# ProProject_si5351-clock_2024-06-27.net
KiCad netlist of a schematic drawn in EasyEDA Pro
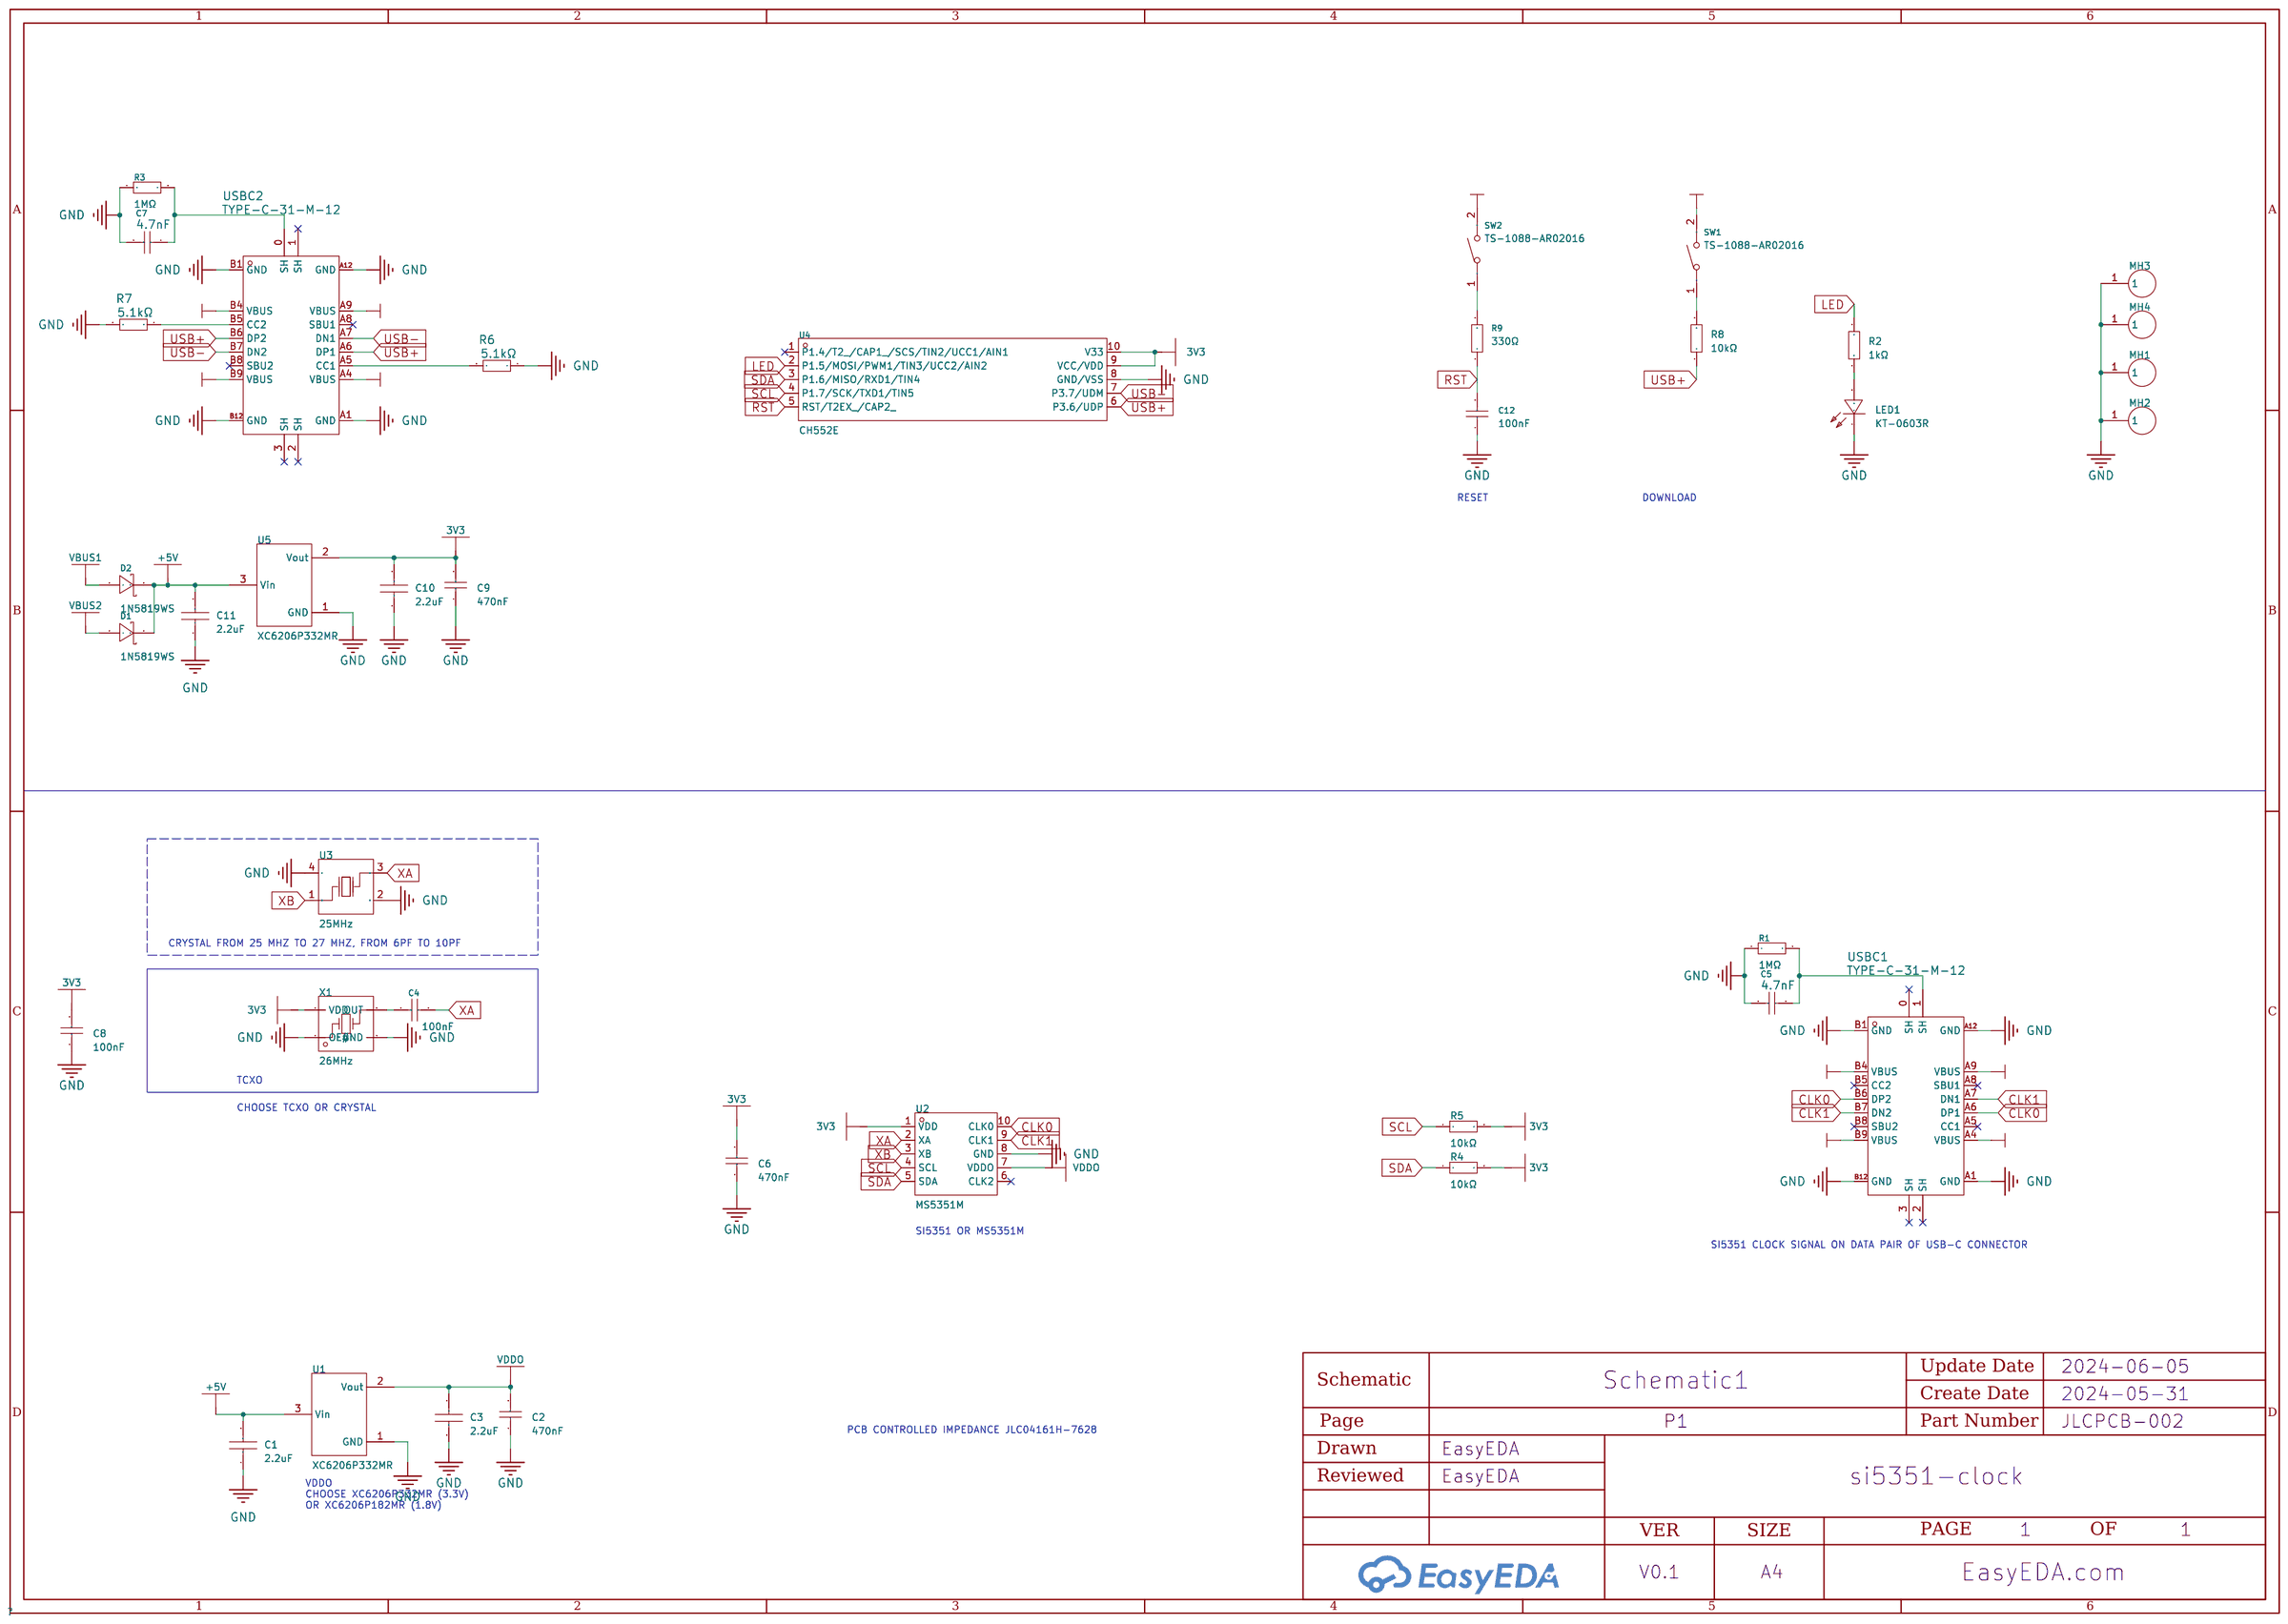
[diagram p0: schematic sheet]

(export (version "E")
  (design (tool "Eeschema 10.0.6"))
  (components
    (comp (ref "C1")
      (value "2.2uF")
      (footprint "easyedapro:C0402")
      (fields
        (field (name "Manufacturer Part") "CL05A225MQ5NSNC")
        (field (name "Manufacturer") "SAMSUNG(三星)")
      )
      (libsource (lib "easyedapro") (part "CL05A225MQ5NSNC"))
    )
    (comp (ref "C2")
      (value "470nF")
      (footprint "easyedapro:C0402")
      (fields
        (field (name "Manufacturer Part") "CL05A474KP5NNNC")
        (field (name "Manufacturer") "SAMSUNG(三星)")
      )
      (libsource (lib "easyedapro") (part "CL05A474KP5NNNC"))
    )
    (comp (ref "C3")
      (value "2.2uF")
      (footprint "easyedapro:C0402")
      (fields
        (field (name "Manufacturer Part") "CL05A225MQ5NSNC")
        (field (name "Manufacturer") "SAMSUNG(三星)")
      )
      (libsource (lib "easyedapro") (part "CL05A225MQ5NSNC"))
    )
    (comp (ref "C4")
      (value "100nF")
      (footprint "easyedapro:C0402")
      (fields
        (field (name "Manufacturer Part") "CL05B104KO5NNNC")
        (field (name "Manufacturer") "SAMSUNG(三星)")
      )
      (libsource (lib "easyedapro") (part "CL05B104KO5NNNC"))
    )
    (comp (ref "C5")
      (value "4.7nF")
      (footprint "easyedapro:C0402")
      (fields (field (name "Manufacturer Part") "0402B472K500NT") (field (name "Manufacturer") "FH(风华)"))
      (libsource (lib "easyedapro") (part "4.7nF"))
    )
    (comp (ref "C6")
      (value "470nF")
      (footprint "easyedapro:C0402")
      (fields
        (field (name "Manufacturer Part") "CL05A474KP5NNNC")
        (field (name "Manufacturer") "SAMSUNG(三星)")
      )
      (libsource (lib "easyedapro") (part "CL05A474KP5NNNC"))
    )
    (comp (ref "C7")
      (value "4.7nF")
      (footprint "easyedapro:C0402")
      (fields (field (name "Manufacturer Part") "0402B472K500NT") (field (name "Manufacturer") "FH(风华)"))
      (libsource (lib "easyedapro") (part "4.7nF"))
    )
    (comp (ref "C8")
      (value "100nF")
      (footprint "easyedapro:C0402")
      (fields
        (field (name "Manufacturer Part") "CL05B104KO5NNNC")
        (field (name "Manufacturer") "SAMSUNG(三星)")
      )
      (libsource (lib "easyedapro") (part "CL05B104KO5NNNC"))
    )
    (comp (ref "C9")
      (value "470nF")
      (footprint "easyedapro:C0402")
      (fields
        (field (name "Manufacturer Part") "CL05A474KP5NNNC")
        (field (name "Manufacturer") "SAMSUNG(三星)")
      )
      (libsource (lib "easyedapro") (part "CL05A474KP5NNNC"))
    )
    (comp (ref "C10")
      (value "2.2uF")
      (footprint "easyedapro:C0402")
      (fields
        (field (name "Manufacturer Part") "CL05A225MQ5NSNC")
        (field (name "Manufacturer") "SAMSUNG(三星)")
      )
      (libsource (lib "easyedapro") (part "CL05A225MQ5NSNC"))
    )
    (comp (ref "C11")
      (value "2.2uF")
      (footprint "easyedapro:C0402")
      (fields
        (field (name "Manufacturer Part") "CL05A225MQ5NSNC")
        (field (name "Manufacturer") "SAMSUNG(三星)")
      )
      (libsource (lib "easyedapro") (part "CL05A225MQ5NSNC"))
    )
    (comp (ref "C12")
      (value "100nF")
      (footprint "easyedapro:C0402")
      (fields
        (field (name "Manufacturer Part") "CL05B104KO5NNNC")
        (field (name "Manufacturer") "SAMSUNG(三星)")
      )
      (libsource (lib "easyedapro") (part "CL05B104KO5NNNC"))
    )
    (comp (ref "D1")
      (value "1N5819WS")
      (footprint "easyedapro:SOD-323_L1.8-W1.3-LS2.5-RD")
      (description "Forward Voltage (Vf@If):600mV@1A Reverse Voltage (Vr):40V Average Rectified Current (Io):1A")
      (fields (field (name "Manufacturer") "Hottech(合科泰)"))
      (libsource (lib "easyedapro") (part "1N5819WS"))
    )
    (comp (ref "D2")
      (value "1N5819WS")
      (footprint "easyedapro:SOD-323_L1.8-W1.3-LS2.5-RD")
      (description "Forward Voltage (Vf@If):600mV@1A Reverse Voltage (Vr):40V Average Rectified Current (Io):1A")
      (fields (field (name "Manufacturer") "Hottech(合科泰)"))
      (libsource (lib "easyedapro") (part "1N5819WS"))
    )
    (comp (ref "LED1")
      (value "KT-0603R")
      (footprint "easyedapro:LED0603-RD")
      (fields (field (name "Manufacturer") "KENTO"))
      (libsource (lib "easyedapro") (part "KT-0603R"))
    )
    (comp (ref "MH1")
      (value "~")
      (footprint "easyedapro:3.2mm MountingHole")
      (description "M3")
      (libsource (lib "easyedapro") (part "3.2mm Mounting Hole"))
    )
    (comp (ref "MH2")
      (value "~")
      (footprint "easyedapro:3.2mm MountingHole")
      (description "M3")
      (libsource (lib "easyedapro") (part "3.2mm Mounting Hole"))
    )
    (comp (ref "MH3")
      (value "~")
      (footprint "easyedapro:3.2mm MountingHole")
      (description "M3")
      (libsource (lib "easyedapro") (part "3.2mm Mounting Hole"))
    )
    (comp (ref "MH4")
      (value "~")
      (footprint "easyedapro:3.2mm MountingHole")
      (description "M3")
      (libsource (lib "easyedapro") (part "3.2mm Mounting Hole"))
    )
    (comp (ref "R1")
      (value "1MΩ")
      (footprint "easyedapro:R0402")
      (fields
        (field (name "Manufacturer Part") "0402WGF1004TCE")
        (field (name "Manufacturer") "UNI-ROYAL(厚声)")
      )
      (libsource (lib "easyedapro") (part "0402WGF1004TCE"))
    )
    (comp (ref "R2")
      (value "1kΩ")
      (footprint "easyedapro:R0402")
      (fields
        (field (name "Manufacturer Part") "0402WGF1001TCE")
        (field (name "Manufacturer") "UNI-ROYAL(厚声)")
      )
      (libsource (lib "easyedapro") (part "0402WGF1001TCE"))
    )
    (comp (ref "R3")
      (value "1MΩ")
      (footprint "easyedapro:R0402")
      (fields
        (field (name "Manufacturer Part") "0402WGF1004TCE")
        (field (name "Manufacturer") "UNI-ROYAL(厚声)")
      )
      (libsource (lib "easyedapro") (part "0402WGF1004TCE"))
    )
    (comp (ref "R4")
      (value "10kΩ")
      (footprint "easyedapro:R0402")
      (fields
        (field (name "Manufacturer Part") "0402WGF1002TCE")
        (field (name "Manufacturer") "UNI-ROYAL(厚声)")
      )
      (libsource (lib "easyedapro") (part "0402WGF1002TCE"))
    )
    (comp (ref "R5")
      (value "10kΩ")
      (footprint "easyedapro:R0402")
      (fields
        (field (name "Manufacturer Part") "0402WGF1002TCE")
        (field (name "Manufacturer") "UNI-ROYAL(厚声)")
      )
      (libsource (lib "easyedapro") (part "0402WGF1002TCE"))
    )
    (comp (ref "R6")
      (value "5.1kΩ")
      (footprint "easyedapro:R0402")
      (fields
        (field (name "Manufacturer Part") "0402WGF5101TCE")
        (field (name "Manufacturer") "UNI-ROYAL(厚声)")
      )
      (libsource (lib "easyedapro") (part "5.1kΩ"))
    )
    (comp (ref "R7")
      (value "5.1kΩ")
      (footprint "easyedapro:R0402")
      (fields
        (field (name "Manufacturer Part") "0402WGF5101TCE")
        (field (name "Manufacturer") "UNI-ROYAL(厚声)")
      )
      (libsource (lib "easyedapro") (part "5.1kΩ"))
    )
    (comp (ref "R8")
      (value "10kΩ")
      (footprint "easyedapro:R0402")
      (fields
        (field (name "Manufacturer Part") "0402WGF1002TCE")
        (field (name "Manufacturer") "UNI-ROYAL(厚声)")
      )
      (libsource (lib "easyedapro") (part "0402WGF1002TCE"))
    )
    (comp (ref "R9")
      (value "330Ω")
      (footprint "easyedapro:R0402")
      (fields
        (field (name "Manufacturer Part") "0402WGF3300TCE")
        (field (name "Manufacturer") "UNI-ROYAL(厚声)")
      )
      (libsource (lib "easyedapro") (part "0402WGF3300TCE"))
    )
    (comp (ref "SW1")
      (value "TS-1088-AR02016")
      (footprint "easyedapro:SW-SMD_L3.9-W3.0-P4.45")
      (fields (field (name "Manufacturer") "XUNPU(讯普)"))
      (libsource (lib "easyedapro") (part "TS-1088-AR02016"))
    )
    (comp (ref "SW2")
      (value "TS-1088-AR02016")
      (footprint "easyedapro:SW-SMD_L3.9-W3.0-P4.45")
      (fields (field (name "Manufacturer") "XUNPU(讯普)"))
      (libsource (lib "easyedapro") (part "TS-1088-AR02016"))
    )
    (comp (ref "U1")
      (value "XC6206P332MR")
      (footprint "easyedapro:SOT-23-3_L2.9-W1.6-P1.90-LS2.8-BR")
      (fields (field (name "Manufacturer") "TOREX(特瑞仕)"))
      (libsource (lib "easyedapro") (part "XC6206P332MR"))
    )
    (comp (ref "U2")
      (value "MS5351M")
      (footprint "easyedapro:MSOP-10_L3.0-W3.0-P0.50-LS5.0-BL")
      (fields (field (name "Manufacturer") "杭州瑞盟"))
      (libsource (lib "easyedapro") (part "MS5351M"))
    )
    (comp (ref "U3")
      (value "25MHz")
      (footprint "easyedapro:CRYSTAL-SMD_4P-L3.2-W2.5-BL-1")
      (fields
        (field (name "Manufacturer Part") "3225-25-10-10-10/A")
        (field (name "Manufacturer") "LIMING(利明)")
      )
      (libsource (lib "easyedapro") (part "3225-25-10-10-10/A"))
    )
    (comp (ref "U4")
      (value "CH552E")
      (footprint "easyedapro:MSOP-10_L3.0-W3.0-P0.50-LS5.0-BL")
      (fields (field (name "Manufacturer") "WCH(南京沁恒)"))
      (libsource (lib "easyedapro") (part "CH552E"))
    )
    (comp (ref "U5")
      (value "XC6206P332MR")
      (footprint "easyedapro:SOT-23-3_L2.9-W1.6-P1.90-LS2.8-BR")
      (fields (field (name "Manufacturer") "TOREX(特瑞仕)"))
      (libsource (lib "easyedapro") (part "XC6206P332MR"))
    )
    (comp (ref "USBC1")
      (value "TYPE-C-31-M-12")
      (footprint "easyedapro:USB-C_SMD-TYPE-C-31-M-12")
      (fields (field (name "Manufacturer") "韩国韩荣"))
      (libsource (lib "easyedapro") (part "TYPE-C-31-M-12"))
    )
    (comp (ref "USBC2")
      (value "TYPE-C-31-M-12")
      (footprint "easyedapro:USB-C_SMD-TYPE-C-31-M-12")
      (fields (field (name "Manufacturer") "韩国韩荣"))
      (libsource (lib "easyedapro") (part "TYPE-C-31-M-12"))
    )
    (comp (ref "X1")
      (value "26MHz")
      (footprint "easyedapro:OSC-SMD_4P-L3.2-W2.5-BL_1XTV")
      (fields (field (name "Manufacturer Part") "1XTW26000MAA") (field (name "Manufacturer") "KDS(大真空)"))
      (libsource (lib "easyedapro") (part "1XTW26000MAA"))
    )
  )
  (nets
    (net (code "1") (name "+5V") (class "Default")
      (node (ref "C1") (pin "2") (pinfunction "2_2") (pintype "unspecified"))
      (node (ref "C11") (pin "2") (pinfunction "2_2") (pintype "unspecified"))
      (node (ref "D1") (pin "1") (pinfunction "K_1") (pintype "input"))
      (node (ref "D2") (pin "1") (pinfunction "K_1") (pintype "input"))
      (node (ref "U1") (pin "3") (pinfunction "Vin_3") (pintype "input"))
      (node (ref "U5") (pin "3") (pinfunction "Vin_3") (pintype "input"))
    )
    (net (code "2") (name "3V3") (class "Default")
      (node (ref "C10") (pin "2") (pinfunction "2_2") (pintype "unspecified"))
      (node (ref "C6") (pin "2") (pinfunction "2_2") (pintype "input"))
      (node (ref "C8") (pin "2") (pinfunction "2_2") (pintype "input"))
      (node (ref "C9") (pin "2") (pinfunction "2_2") (pintype "input"))
      (node (ref "R4") (pin "2") (pinfunction "2_2") (pintype "input"))
      (node (ref "R5") (pin "2") (pinfunction "2_2") (pintype "input"))
      (node (ref "SW1") (pin "2") (pinfunction "2_2") (pintype "input"))
      (node (ref "SW2") (pin "2") (pinfunction "2_2") (pintype "input"))
      (node (ref "U2") (pin "1") (pinfunction "VDD_1") (pintype "input"))
      (node (ref "U4") (pin "10") (pinfunction "V33_10") (pintype "input"))
      (node (ref "U4") (pin "9") (pinfunction "VCC/VDD_9") (pintype "input"))
      (node (ref "U5") (pin "2") (pinfunction "Vout_2") (pintype "input"))
      (node (ref "X1") (pin "4") (pinfunction "VDD_4") (pintype "input"))
    )
    (net (code "3") (name "CLK0") (class "Default")
      (node (ref "U2") (pin "10") (pinfunction "CLK0_10") (pintype "input"))
      (node (ref "USBC1") (pin "A6") (pinfunction "DP1_A6") (pintype "input"))
      (node (ref "USBC1") (pin "B6") (pinfunction "DP2_B6") (pintype "input"))
    )
    (net (code "4") (name "CLK1") (class "Default")
      (node (ref "U2") (pin "9") (pinfunction "CLK1_9") (pintype "input"))
      (node (ref "USBC1") (pin "A7") (pinfunction "DN1_A7") (pintype "input"))
      (node (ref "USBC1") (pin "B7") (pinfunction "DN2_B7") (pintype "input"))
    )
    (net (code "5") (name "GND") (class "Default")
      (node (ref "C1") (pin "1") (pinfunction "1_1") (pintype "unspecified"))
      (node (ref "C10") (pin "1") (pinfunction "1_1") (pintype "unspecified"))
      (node (ref "C11") (pin "1") (pinfunction "1_1") (pintype "unspecified"))
      (node (ref "C12") (pin "1") (pinfunction "1_1") (pintype "input"))
      (node (ref "C2") (pin "1") (pinfunction "1_1") (pintype "input"))
      (node (ref "C3") (pin "1") (pinfunction "1_1") (pintype "unspecified"))
      (node (ref "C5") (pin "1") (pinfunction "1_1") (pintype "input"))
      (node (ref "C6") (pin "1") (pinfunction "1_1") (pintype "input"))
      (node (ref "C7") (pin "1") (pinfunction "1_1") (pintype "input"))
      (node (ref "C8") (pin "1") (pinfunction "1_1") (pintype "input"))
      (node (ref "C9") (pin "1") (pinfunction "1_1") (pintype "input"))
      (node (ref "LED1") (pin "1") (pinfunction "K_1") (pintype "input"))
      (node (ref "MH1") (pin "1") (pinfunction "1_1") (pintype "input"))
      (node (ref "MH2") (pin "1") (pinfunction "1_1") (pintype "input"))
      (node (ref "MH3") (pin "1") (pinfunction "1_1") (pintype "input"))
      (node (ref "MH4") (pin "1") (pinfunction "1_1") (pintype "input"))
      (node (ref "R1") (pin "1") (pinfunction "1_1") (pintype "input"))
      (node (ref "R3") (pin "1") (pinfunction "1_1") (pintype "input"))
      (node (ref "R6") (pin "1") (pinfunction "1_1") (pintype "input"))
      (node (ref "R7") (pin "2") (pinfunction "2_2") (pintype "input"))
      (node (ref "U1") (pin "1") (pinfunction "GND_1") (pintype "input"))
      (node (ref "U2") (pin "8") (pinfunction "GND_8") (pintype "input"))
      (node (ref "U3") (pin "2") (pinfunction "GND_2") (pintype "unspecified"))
      (node (ref "U3") (pin "4") (pinfunction "GND_4") (pintype "unspecified"))
      (node (ref "U4") (pin "8") (pinfunction "GND/VSS_8") (pintype "input"))
      (node (ref "U5") (pin "1") (pinfunction "GND_1") (pintype "input"))
      (node (ref "USBC1") (pin "A1") (pinfunction "GND_A1") (pintype "input"))
      (node (ref "USBC1") (pin "A12") (pinfunction "GND_A12") (pintype "input"))
      (node (ref "USBC1") (pin "B1") (pinfunction "GND_B1") (pintype "input"))
      (node (ref "USBC1") (pin "B12") (pinfunction "GND_B12") (pintype "input"))
      (node (ref "USBC2") (pin "A1") (pinfunction "GND_A1") (pintype "input"))
      (node (ref "USBC2") (pin "A12") (pinfunction "GND_A12") (pintype "input"))
      (node (ref "USBC2") (pin "B1") (pinfunction "GND_B1") (pintype "input"))
      (node (ref "USBC2") (pin "B12") (pinfunction "GND_B12") (pintype "input"))
      (node (ref "X1") (pin "1") (pinfunction "OE#_1") (pintype "input"))
      (node (ref "X1") (pin "2") (pinfunction "GND_2") (pintype "input"))
    )
    (net (code "6") (name "LED") (class "Default")
      (node (ref "R2") (pin "2") (pinfunction "2_2") (pintype "input"))
      (node (ref "U4") (pin "2") (pinfunction "P1.5/MOSI/PWM1/TIN3/UCC2/AIN2_2") (pintype "input"))
    )
    (net (code "7") (name "Net-(C5-Pad2)") (class "Default")
      (node (ref "C5") (pin "2") (pinfunction "2_2") (pintype "input"))
      (node (ref "R1") (pin "2") (pinfunction "2_2") (pintype "input"))
      (node (ref "USBC1") (pin "1") (pinfunction "SH_1") (pintype "input"))
    )
    (net (code "8") (name "Net-(C7-Pad2)") (class "Default")
      (node (ref "C7") (pin "2") (pinfunction "2_2") (pintype "input"))
      (node (ref "R3") (pin "2") (pinfunction "2_2") (pintype "input"))
      (node (ref "USBC2") (pin "0") (pinfunction "SH_0") (pintype "input"))
    )
    (net (code "9") (name "Net-(LED1-A)") (class "Default")
      (node (ref "LED1") (pin "2") (pinfunction "A_2") (pintype "input"))
      (node (ref "R2") (pin "1") (pinfunction "1_1") (pintype "input"))
    )
    (net (code "10") (name "Net-(R8-Pad2)") (class "Default")
      (node (ref "R8") (pin "2") (pinfunction "2_2") (pintype "input"))
      (node (ref "SW1") (pin "1") (pinfunction "1_1") (pintype "input"))
    )
    (net (code "11") (name "Net-(R9-Pad2)") (class "Default")
      (node (ref "R9") (pin "2") (pinfunction "2_2") (pintype "input"))
      (node (ref "SW2") (pin "1") (pinfunction "1_1") (pintype "input"))
    )
    (net (code "12") (name "Net-(USBC2-CC1)") (class "Default")
      (node (ref "R6") (pin "2") (pinfunction "2_2") (pintype "input"))
      (node (ref "USBC2") (pin "A5") (pinfunction "CC1_A5") (pintype "input"))
    )
    (net (code "13") (name "Net-(USBC2-CC2)") (class "Default")
      (node (ref "R7") (pin "1") (pinfunction "1_1") (pintype "input"))
      (node (ref "USBC2") (pin "B5") (pinfunction "CC2_B5") (pintype "input"))
    )
    (net (code "14") (name "Net-(X1-OUT)") (class "Default")
      (node (ref "C4") (pin "1") (pinfunction "1_1") (pintype "input"))
      (node (ref "X1") (pin "3") (pinfunction "OUT_3") (pintype "input"))
    )
    (net (code "15") (name "RST") (class "Default")
      (node (ref "C12") (pin "2") (pinfunction "2_2") (pintype "input"))
      (node (ref "R9") (pin "1") (pinfunction "1_1") (pintype "input"))
      (node (ref "U4") (pin "5") (pinfunction "RST/T2EX_/CAP2__5") (pintype "input"))
    )
    (net (code "16") (name "SCL") (class "Default")
      (node (ref "R5") (pin "1") (pinfunction "1_1") (pintype "input"))
      (node (ref "U2") (pin "4") (pinfunction "SCL_4") (pintype "input"))
      (node (ref "U4") (pin "4") (pinfunction "P1.7/SCK/TXD1/TIN5_4") (pintype "input"))
    )
    (net (code "17") (name "SDA") (class "Default")
      (node (ref "R4") (pin "1") (pinfunction "1_1") (pintype "input"))
      (node (ref "U2") (pin "5") (pinfunction "SDA_5") (pintype "input"))
      (node (ref "U4") (pin "3") (pinfunction "P1.6/MISO/RXD1/TIN4_3") (pintype "input"))
    )
    (net (code "18") (name "USB+") (class "Default")
      (node (ref "R8") (pin "1") (pinfunction "1_1") (pintype "input"))
      (node (ref "U4") (pin "6") (pinfunction "P3.6/UDP_6") (pintype "input"))
      (node (ref "USBC2") (pin "A6") (pinfunction "DP1_A6") (pintype "input"))
      (node (ref "USBC2") (pin "B6") (pinfunction "DP2_B6") (pintype "input"))
    )
    (net (code "19") (name "USB-") (class "Default")
      (node (ref "U4") (pin "7") (pinfunction "P3.7/UDM_7") (pintype "input"))
      (node (ref "USBC2") (pin "A7") (pinfunction "DN1_A7") (pintype "input"))
      (node (ref "USBC2") (pin "B7") (pinfunction "DN2_B7") (pintype "input"))
    )
    (net (code "20") (name "VBUS1") (class "Default")
      (node (ref "D2") (pin "2") (pinfunction "A_2") (pintype "input"))
      (node (ref "USBC2") (pin "A4") (pinfunction "VBUS_A4") (pintype "input"))
      (node (ref "USBC2") (pin "A9") (pinfunction "VBUS_A9") (pintype "input"))
      (node (ref "USBC2") (pin "B4") (pinfunction "VBUS_B4") (pintype "input"))
      (node (ref "USBC2") (pin "B9") (pinfunction "VBUS_B9") (pintype "input"))
    )
    (net (code "21") (name "VBUS2") (class "Default")
      (node (ref "D1") (pin "2") (pinfunction "A_2") (pintype "input"))
      (node (ref "USBC1") (pin "A4") (pinfunction "VBUS_A4") (pintype "input"))
      (node (ref "USBC1") (pin "A9") (pinfunction "VBUS_A9") (pintype "input"))
      (node (ref "USBC1") (pin "B4") (pinfunction "VBUS_B4") (pintype "input"))
      (node (ref "USBC1") (pin "B9") (pinfunction "VBUS_B9") (pintype "input"))
    )
    (net (code "22") (name "VDDO") (class "Default")
      (node (ref "C2") (pin "2") (pinfunction "2_2") (pintype "input"))
      (node (ref "C3") (pin "2") (pinfunction "2_2") (pintype "unspecified"))
      (node (ref "U1") (pin "2") (pinfunction "Vout_2") (pintype "input"))
      (node (ref "U2") (pin "7") (pinfunction "VDDO_7") (pintype "input"))
    )
    (net (code "23") (name "XA") (class "Default")
      (node (ref "C4") (pin "2") (pinfunction "2_2") (pintype "input"))
      (node (ref "U2") (pin "2") (pinfunction "XA_2") (pintype "input"))
      (node (ref "U3") (pin "3") (pinfunction "OSC2_3") (pintype "unspecified"))
    )
    (net (code "24") (name "XB") (class "Default")
      (node (ref "U2") (pin "3") (pinfunction "XB_3") (pintype "input"))
      (node (ref "U3") (pin "1") (pinfunction "OSC1_1") (pintype "unspecified"))
    )
    (net (code "25") (name "unconnected-(U2-CLK2-Pad6)") (class "Default")
      (node (ref "U2") (pin "6") (pinfunction "CLK2_6") (pintype "input+no_connect"))
    )
    (net (code "26") (name "unconnected-(U4-P1.4{slash}T2_{slash}CAP1_{slash}SCS{slash}TIN2{slash}UCC1{slash}AIN1-Pad1)") (class "Default")
      (node (ref "U4") (pin "1") (pinfunction "P1.4/T2_/CAP1_/SCS/TIN2/UCC1/AIN1_1") (pintype "input+no_connect"))
    )
    (net (code "27") (name "unconnected-(USBC1-CC1-PadA5)") (class "Default")
      (node (ref "USBC1") (pin "A5") (pinfunction "CC1_A5") (pintype "input+no_connect"))
    )
    (net (code "28") (name "unconnected-(USBC1-CC2-PadB5)") (class "Default")
      (node (ref "USBC1") (pin "B5") (pinfunction "CC2_B5") (pintype "input+no_connect"))
    )
    (net (code "29") (name "unconnected-(USBC1-SBU1-PadA8)") (class "Default")
      (node (ref "USBC1") (pin "A8") (pinfunction "SBU1_A8") (pintype "input+no_connect"))
    )
    (net (code "30") (name "unconnected-(USBC1-SBU2-PadB8)") (class "Default")
      (node (ref "USBC1") (pin "B8") (pinfunction "SBU2_B8") (pintype "input+no_connect"))
    )
    (net (code "31") (name "unconnected-(USBC1-SH-Pad0)") (class "Default")
      (node (ref "USBC1") (pin "0") (pinfunction "SH_0") (pintype "input+no_connect"))
    )
    (net (code "32") (name "unconnected-(USBC1-SH-Pad2)") (class "Default")
      (node (ref "USBC1") (pin "2") (pinfunction "SH_2") (pintype "input+no_connect"))
    )
    (net (code "33") (name "unconnected-(USBC1-SH-Pad3)") (class "Default")
      (node (ref "USBC1") (pin "3") (pinfunction "SH_3") (pintype "input+no_connect"))
    )
    (net (code "34") (name "unconnected-(USBC2-SBU1-PadA8)") (class "Default")
      (node (ref "USBC2") (pin "A8") (pinfunction "SBU1_A8") (pintype "input+no_connect"))
    )
    (net (code "35") (name "unconnected-(USBC2-SBU2-PadB8)") (class "Default")
      (node (ref "USBC2") (pin "B8") (pinfunction "SBU2_B8") (pintype "input+no_connect"))
    )
    (net (code "36") (name "unconnected-(USBC2-SH-Pad1)") (class "Default")
      (node (ref "USBC2") (pin "1") (pinfunction "SH_1") (pintype "input+no_connect"))
    )
    (net (code "37") (name "unconnected-(USBC2-SH-Pad2)") (class "Default")
      (node (ref "USBC2") (pin "2") (pinfunction "SH_2") (pintype "input+no_connect"))
    )
    (net (code "38") (name "unconnected-(USBC2-SH-Pad3)") (class "Default")
      (node (ref "USBC2") (pin "3") (pinfunction "SH_3") (pintype "input+no_connect"))
    )
  )
)
